# MAIN.net
KiCad netlist of a schematic drawn in Altium Designer
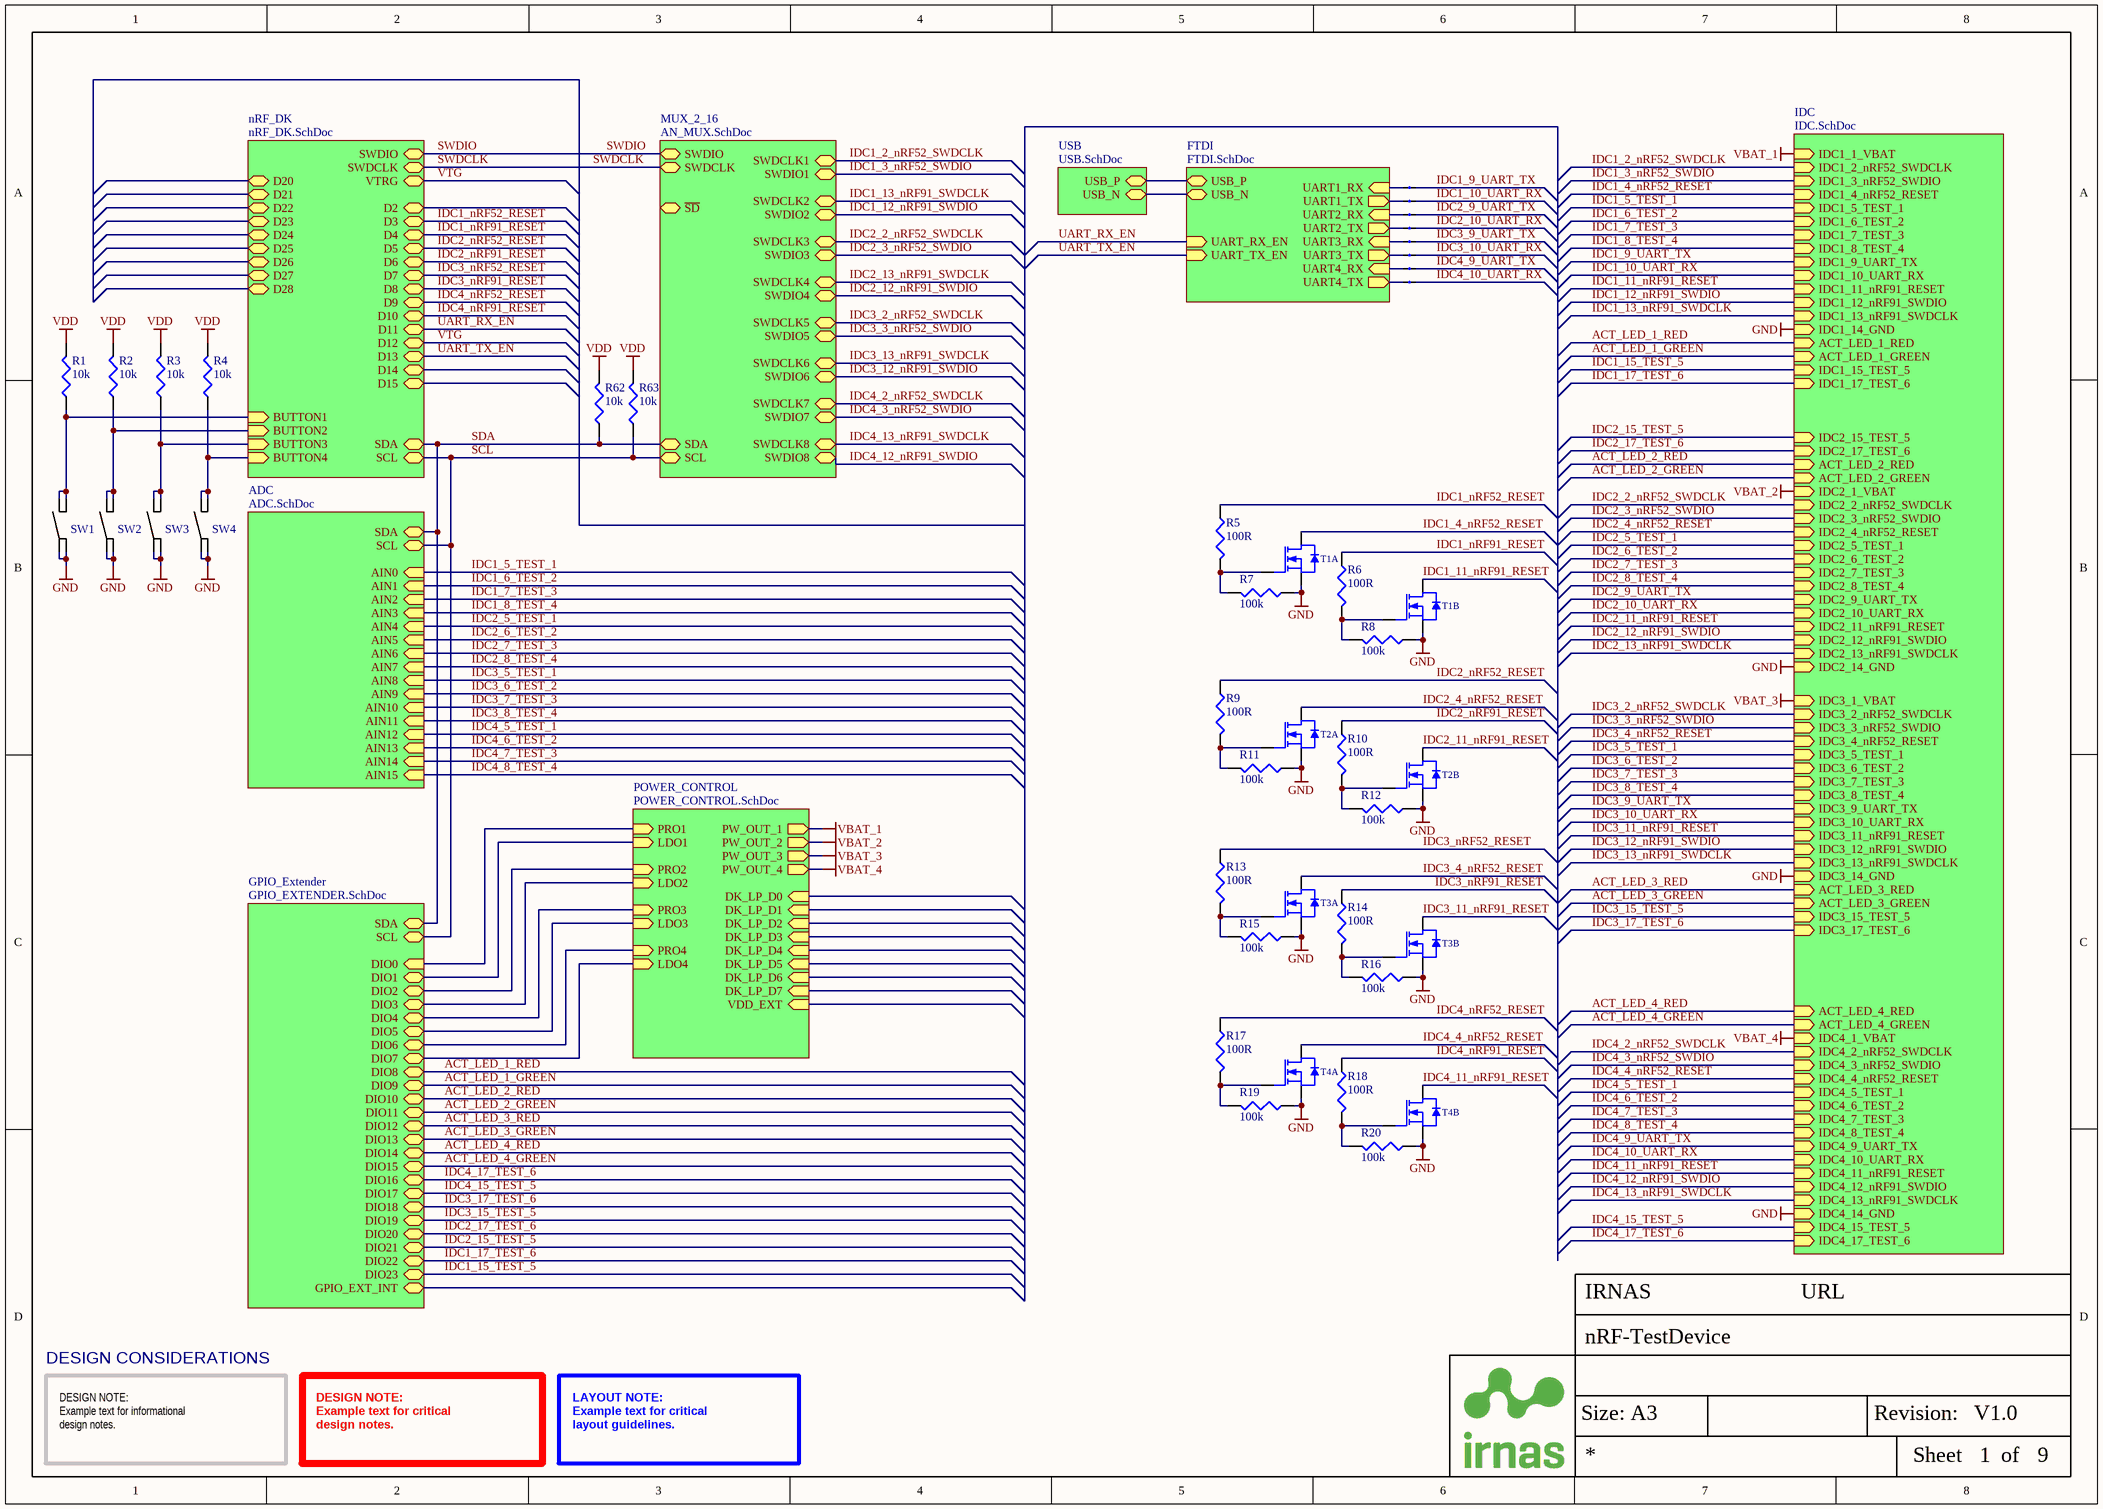
[diagram p0: MAIN.SchDoc]

(export (version "E")
  (design (tool "Eeschema 10.0.6"))
  (components
    (comp (ref "NT1")
      (value "~")
      (footprint "2 PIN STARPOINT")
      (description "Starpoint")
      (libsource (lib "Passive") (part "NetTie"))
    )
    (comp (ref "NT2")
      (value "~")
      (footprint "2 PIN STARPOINT")
      (description "Starpoint")
      (libsource (lib "Passive") (part "NetTie"))
    )
    (comp (ref "NT3")
      (value "~")
      (footprint "2 PIN STARPOINT")
      (description "Starpoint")
      (libsource (lib "Passive") (part "NetTie"))
    )
    (comp (ref "NT4")
      (value "~")
      (footprint "2 PIN STARPOINT")
      (description "Starpoint")
      (libsource (lib "Passive") (part "NetTie"))
    )
    (comp (ref "NT5")
      (value "~")
      (footprint "2 PIN STARPOINT")
      (description "Starpoint")
      (libsource (lib "Passive") (part "NetTie"))
    )
    (comp (ref "NT6")
      (value "~")
      (footprint "2 PIN STARPOINT")
      (description "Starpoint")
      (libsource (lib "Passive") (part "NetTie"))
    )
    (comp (ref "NT7")
      (value "~")
      (footprint "2 PIN STARPOINT")
      (description "Starpoint")
      (libsource (lib "Passive") (part "NetTie"))
    )
    (comp (ref "NT8")
      (value "~")
      (footprint "2 PIN STARPOINT")
      (description "Starpoint")
      (libsource (lib "Passive") (part "NetTie"))
    )
    (comp (ref "R1")
      (value "10k")
      (footprint "RES0402")
      (fields
        (field (name "MANUFACTURER") "Multicomp")
        (field (name "MANUFACTURER PART NUMBER") "MCWR04X1002FTL")
        (field (name "TOLERANCE") "1%")
      )
      (libsource (lib "Passive") (part "R - 10k/0402"))
    )
    (comp (ref "R2")
      (value "10k")
      (footprint "RES0402")
      (fields
        (field (name "MANUFACTURER") "Multicomp")
        (field (name "MANUFACTURER PART NUMBER") "MCWR04X1002FTL")
        (field (name "TOLERANCE") "1%")
      )
      (libsource (lib "Passive") (part "R - 10k/0402"))
    )
    (comp (ref "R3")
      (value "10k")
      (footprint "RES0402")
      (fields
        (field (name "MANUFACTURER") "Multicomp")
        (field (name "MANUFACTURER PART NUMBER") "MCWR04X1002FTL")
        (field (name "TOLERANCE") "1%")
      )
      (libsource (lib "Passive") (part "R - 10k/0402"))
    )
    (comp (ref "R4")
      (value "10k")
      (footprint "RES0402")
      (fields
        (field (name "MANUFACTURER") "Multicomp")
        (field (name "MANUFACTURER PART NUMBER") "MCWR04X1002FTL")
        (field (name "TOLERANCE") "1%")
      )
      (libsource (lib "Passive") (part "R - 10k/0402"))
    )
    (comp (ref "R5")
      (value "100R")
      (footprint "RES0402")
      (fields
        (field (name "MANUFACTURER") "Multicomp")
        (field (name "MANUFACTURER PART NUMBER") "MCMR04X1000FTL")
        (field (name "TOLERANCE") "1%")
      )
      (libsource (lib "Passive") (part "R - 100R/0402"))
    )
    (comp (ref "R6")
      (value "100R")
      (footprint "RES0402")
      (fields
        (field (name "MANUFACTURER") "Multicomp")
        (field (name "MANUFACTURER PART NUMBER") "MCMR04X1000FTL")
        (field (name "TOLERANCE") "1%")
      )
      (libsource (lib "Passive") (part "R - 100R/0402"))
    )
    (comp (ref "R7")
      (value "100k")
      (footprint "RES0402")
      (description "MULTICOMP   MCWR04X1003FTL   RES, THICK FILM, 100KOHM, 1%, 0.0625W")
      (fields
        (field (name "MANUFACTURER") "Multicomp")
        (field (name "MANUFACTURER PART NUMBER") "MCWR04X1003FTL")
      )
      (libsource (lib "Passive") (part "R - 100k/0402"))
    )
    (comp (ref "R8")
      (value "100k")
      (footprint "RES0402")
      (description "MULTICOMP   MCWR04X1003FTL   RES, THICK FILM, 100KOHM, 1%, 0.0625W")
      (fields
        (field (name "MANUFACTURER") "Multicomp")
        (field (name "MANUFACTURER PART NUMBER") "MCWR04X1003FTL")
      )
      (libsource (lib "Passive") (part "R - 100k/0402"))
    )
    (comp (ref "R9")
      (value "100R")
      (footprint "RES0402")
      (fields
        (field (name "MANUFACTURER") "Multicomp")
        (field (name "MANUFACTURER PART NUMBER") "MCMR04X1000FTL")
        (field (name "TOLERANCE") "1%")
      )
      (libsource (lib "Passive") (part "R - 100R/0402"))
    )
    (comp (ref "R10")
      (value "100R")
      (footprint "RES0402")
      (fields
        (field (name "MANUFACTURER") "Multicomp")
        (field (name "MANUFACTURER PART NUMBER") "MCMR04X1000FTL")
        (field (name "TOLERANCE") "1%")
      )
      (libsource (lib "Passive") (part "R - 100R/0402"))
    )
    (comp (ref "R11")
      (value "100k")
      (footprint "RES0402")
      (description "MULTICOMP   MCWR04X1003FTL   RES, THICK FILM, 100KOHM, 1%, 0.0625W")
      (fields
        (field (name "MANUFACTURER") "Multicomp")
        (field (name "MANUFACTURER PART NUMBER") "MCWR04X1003FTL")
      )
      (libsource (lib "Passive") (part "R - 100k/0402"))
    )
    (comp (ref "R12")
      (value "100k")
      (footprint "RES0402")
      (description "MULTICOMP   MCWR04X1003FTL   RES, THICK FILM, 100KOHM, 1%, 0.0625W")
      (fields
        (field (name "MANUFACTURER") "Multicomp")
        (field (name "MANUFACTURER PART NUMBER") "MCWR04X1003FTL")
      )
      (libsource (lib "Passive") (part "R - 100k/0402"))
    )
    (comp (ref "R13")
      (value "100R")
      (footprint "RES0402")
      (fields
        (field (name "MANUFACTURER") "Multicomp")
        (field (name "MANUFACTURER PART NUMBER") "MCMR04X1000FTL")
        (field (name "TOLERANCE") "1%")
      )
      (libsource (lib "Passive") (part "R - 100R/0402"))
    )
    (comp (ref "R14")
      (value "100R")
      (footprint "RES0402")
      (fields
        (field (name "MANUFACTURER") "Multicomp")
        (field (name "MANUFACTURER PART NUMBER") "MCMR04X1000FTL")
        (field (name "TOLERANCE") "1%")
      )
      (libsource (lib "Passive") (part "R - 100R/0402"))
    )
    (comp (ref "R15")
      (value "100k")
      (footprint "RES0402")
      (description "MULTICOMP   MCWR04X1003FTL   RES, THICK FILM, 100KOHM, 1%, 0.0625W")
      (fields
        (field (name "MANUFACTURER") "Multicomp")
        (field (name "MANUFACTURER PART NUMBER") "MCWR04X1003FTL")
      )
      (libsource (lib "Passive") (part "R - 100k/0402"))
    )
    (comp (ref "R16")
      (value "100k")
      (footprint "RES0402")
      (description "MULTICOMP   MCWR04X1003FTL   RES, THICK FILM, 100KOHM, 1%, 0.0625W")
      (fields
        (field (name "MANUFACTURER") "Multicomp")
        (field (name "MANUFACTURER PART NUMBER") "MCWR04X1003FTL")
      )
      (libsource (lib "Passive") (part "R - 100k/0402"))
    )
    (comp (ref "R17")
      (value "100R")
      (footprint "RES0402")
      (fields
        (field (name "MANUFACTURER") "Multicomp")
        (field (name "MANUFACTURER PART NUMBER") "MCMR04X1000FTL")
        (field (name "TOLERANCE") "1%")
      )
      (libsource (lib "Passive") (part "R - 100R/0402"))
    )
    (comp (ref "R18")
      (value "100R")
      (footprint "RES0402")
      (fields
        (field (name "MANUFACTURER") "Multicomp")
        (field (name "MANUFACTURER PART NUMBER") "MCMR04X1000FTL")
        (field (name "TOLERANCE") "1%")
      )
      (libsource (lib "Passive") (part "R - 100R/0402"))
    )
    (comp (ref "R19")
      (value "100k")
      (footprint "RES0402")
      (description "MULTICOMP   MCWR04X1003FTL   RES, THICK FILM, 100KOHM, 1%, 0.0625W")
      (fields
        (field (name "MANUFACTURER") "Multicomp")
        (field (name "MANUFACTURER PART NUMBER") "MCWR04X1003FTL")
      )
      (libsource (lib "Passive") (part "R - 100k/0402"))
    )
    (comp (ref "R20")
      (value "100k")
      (footprint "RES0402")
      (description "MULTICOMP   MCWR04X1003FTL   RES, THICK FILM, 100KOHM, 1%, 0.0625W")
      (fields
        (field (name "MANUFACTURER") "Multicomp")
        (field (name "MANUFACTURER PART NUMBER") "MCWR04X1003FTL")
      )
      (libsource (lib "Passive") (part "R - 100k/0402"))
    )
    (comp (ref "R62")
      (value "10k")
      (footprint "RES0402")
      (fields
        (field (name "MANUFACTURER") "Multicomp")
        (field (name "MANUFACTURER PART NUMBER") "MCWR04X1002FTL")
        (field (name "TOLERANCE") "1%")
      )
      (libsource (lib "Passive") (part "R - 10k/0402"))
    )
    (comp (ref "R63")
      (value "10k")
      (footprint "RES0402")
      (fields
        (field (name "MANUFACTURER") "Multicomp")
        (field (name "MANUFACTURER PART NUMBER") "MCWR04X1002FTL")
        (field (name "TOLERANCE") "1%")
      )
      (libsource (lib "Passive") (part "R - 10k/0402"))
    )
    (comp (ref "SW1")
      (value "PTS645SL50-2 LFS")
      (footprint "Tactile Switch THT")
      (description "Tactile Switch, PT645 Series, Top Actuated, Through Hole, Round Button, 130 gf, 50mA at 12VDC")
      (fields (field (name "MANUFACTURER") "C&K"))
      (libsource (lib "Mechanical") (part "SW - PTS645SL50-2 LFS"))
    )
    (comp (ref "SW2")
      (value "PTS645SL50-2 LFS")
      (footprint "Tactile Switch THT")
      (description "Tactile Switch, PT645 Series, Top Actuated, Through Hole, Round Button, 130 gf, 50mA at 12VDC")
      (fields (field (name "MANUFACTURER") "C&K"))
      (libsource (lib "Mechanical") (part "SW - PTS645SL50-2 LFS"))
    )
    (comp (ref "SW3")
      (value "PTS645SL50-2 LFS")
      (footprint "Tactile Switch THT")
      (description "Tactile Switch, PT645 Series, Top Actuated, Through Hole, Round Button, 130 gf, 50mA at 12VDC")
      (fields (field (name "MANUFACTURER") "C&K"))
      (libsource (lib "Mechanical") (part "SW - PTS645SL50-2 LFS"))
    )
    (comp (ref "SW4")
      (value "PTS645SL50-2 LFS")
      (footprint "Tactile Switch THT")
      (description "Tactile Switch, PT645 Series, Top Actuated, Through Hole, Round Button, 130 gf, 50mA at 12VDC")
      (fields (field (name "MANUFACTURER") "C&K"))
      (libsource (lib "Mechanical") (part "SW - PTS645SL50-2 LFS"))
    )
    (comp (ref "T1")
      (value "NTZD3154NT1G")
      (footprint "SOT-563")
      (description "Dual MOSFET, Dual N Channel, 540 mA, 20 V, 0.4 ohm, 4.5 V, 1 V")
      (fields (field (name "AUTHOR") "Ciril Golob"))
      (libsource (lib "Active") (part "T_M - NTZD3154NT1G"))
    )
    (comp (ref "T2")
      (value "NTZD3154NT1G")
      (footprint "SOT-563")
      (description "Dual MOSFET, Dual N Channel, 540 mA, 20 V, 0.4 ohm, 4.5 V, 1 V")
      (fields (field (name "AUTHOR") "Ciril Golob"))
      (libsource (lib "Active") (part "T_M - NTZD3154NT1G"))
    )
    (comp (ref "T3")
      (value "NTZD3154NT1G")
      (footprint "SOT-563")
      (description "Dual MOSFET, Dual N Channel, 540 mA, 20 V, 0.4 ohm, 4.5 V, 1 V")
      (fields (field (name "AUTHOR") "Ciril Golob"))
      (libsource (lib "Active") (part "T_M - NTZD3154NT1G"))
    )
    (comp (ref "T4")
      (value "NTZD3154NT1G")
      (footprint "SOT-563")
      (description "Dual MOSFET, Dual N Channel, 540 mA, 20 V, 0.4 ohm, 4.5 V, 1 V")
      (fields (field (name "AUTHOR") "Ciril Golob"))
      (libsource (lib "Active") (part "T_M - NTZD3154NT1G"))
    )
  )
  (nets
    (net (code "9") (name "/BUTTON1") (class "Default")
      (node (ref "R1") (pin "1") (pinfunction "1_1") (pintype "passive"))
      (node (ref "SW1") (pin "3") (pinfunction "3_3") (pintype "passive"))
      (node (ref "SW1") (pin "4") (pinfunction "4_4") (pintype "passive"))
    )
    (net (code "10") (name "/BUTTON2") (class "Default")
      (node (ref "R2") (pin "1") (pinfunction "1_1") (pintype "passive"))
      (node (ref "SW2") (pin "3") (pinfunction "3_3") (pintype "passive"))
      (node (ref "SW2") (pin "4") (pinfunction "4_4") (pintype "passive"))
    )
    (net (code "11") (name "/BUTTON3") (class "Default")
      (node (ref "R3") (pin "1") (pinfunction "1_1") (pintype "passive"))
      (node (ref "SW3") (pin "3") (pinfunction "3_3") (pintype "passive"))
      (node (ref "SW3") (pin "4") (pinfunction "4_4") (pintype "passive"))
    )
    (net (code "12") (name "/BUTTON4") (class "Default")
      (node (ref "R4") (pin "1") (pinfunction "1_1") (pintype "passive"))
      (node (ref "SW4") (pin "3") (pinfunction "3_3") (pintype "passive"))
      (node (ref "SW4") (pin "4") (pinfunction "4_4") (pintype "passive"))
    )
    (net (code "44") (name "/IDC1_4_nRF52_RESET") (class "Default")
      (node (ref "T1") (pin "6") (pinfunction "D1_6") (pintype "passive"))
    )
    (net (code "49") (name "/IDC1_9_UART_TX") (class "Default")
      (node (ref "NT1") (pin "2") (pintype "passive"))
    )
    (net (code "50") (name "/IDC1_10_UART_RX") (class "Default")
      (node (ref "NT2") (pin "2") (pintype "passive"))
    )
    (net (code "51") (name "/IDC1_11_nRF91_RESET") (class "Default")
      (node (ref "T1") (pin "3") (pinfunction "D2_3") (pintype "passive"))
    )
    (net (code "56") (name "/IDC1_nRF52_RESET") (class "Default")
      (node (ref "R5") (pin "1") (pinfunction "1_1") (pintype "passive"))
    )
    (net (code "57") (name "/IDC1_nRF91_RESET") (class "Default")
      (node (ref "R6") (pin "1") (pinfunction "1_1") (pintype "passive"))
    )
    (net (code "60") (name "/IDC2_4_nRF52_RESET") (class "Default")
      (node (ref "T2") (pin "6") (pinfunction "D1_6") (pintype "passive"))
    )
    (net (code "65") (name "/IDC2_9_UART_TX") (class "Default")
      (node (ref "NT3") (pin "2") (pintype "passive"))
    )
    (net (code "66") (name "/IDC2_10_UART_RX") (class "Default")
      (node (ref "NT4") (pin "2") (pintype "passive"))
    )
    (net (code "67") (name "/IDC2_11_nRF91_RESET") (class "Default")
      (node (ref "T2") (pin "3") (pinfunction "D2_3") (pintype "passive"))
    )
    (net (code "72") (name "/IDC2_nRF52_RESET") (class "Default")
      (node (ref "R9") (pin "1") (pinfunction "1_1") (pintype "passive"))
    )
    (net (code "73") (name "/IDC2_nRF91_RESET") (class "Default")
      (node (ref "R10") (pin "1") (pinfunction "1_1") (pintype "passive"))
    )
    (net (code "76") (name "/IDC3_4_nRF52_RESET") (class "Default")
      (node (ref "T3") (pin "6") (pinfunction "D1_6") (pintype "passive"))
    )
    (net (code "81") (name "/IDC3_9_UART_TX") (class "Default")
      (node (ref "NT5") (pin "2") (pintype "passive"))
    )
    (net (code "82") (name "/IDC3_10_UART_RX") (class "Default")
      (node (ref "NT6") (pin "2") (pintype "passive"))
    )
    (net (code "83") (name "/IDC3_11_nRF91_RESET") (class "Default")
      (node (ref "T3") (pin "3") (pinfunction "D2_3") (pintype "passive"))
    )
    (net (code "88") (name "/IDC3_nRF52_RESET") (class "Default")
      (node (ref "R13") (pin "1") (pinfunction "1_1") (pintype "passive"))
    )
    (net (code "89") (name "/IDC3_nRF91_RESET") (class "Default")
      (node (ref "R14") (pin "1") (pinfunction "1_1") (pintype "passive"))
    )
    (net (code "92") (name "/IDC4_4_nRF52_RESET") (class "Default")
      (node (ref "T4") (pin "6") (pinfunction "D1_6") (pintype "passive"))
    )
    (net (code "97") (name "/IDC4_9_UART_TX") (class "Default")
      (node (ref "NT7") (pin "2") (pintype "passive"))
    )
    (net (code "98") (name "/IDC4_10_UART_RX") (class "Default")
      (node (ref "NT8") (pin "2") (pintype "passive"))
    )
    (net (code "99") (name "/IDC4_11_nRF91_RESET") (class "Default")
      (node (ref "T4") (pin "3") (pinfunction "D2_3") (pintype "passive"))
    )
    (net (code "104") (name "/IDC4_nRF52_RESET") (class "Default")
      (node (ref "R17") (pin "1") (pinfunction "1_1") (pintype "passive"))
    )
    (net (code "105") (name "/IDC4_nRF91_RESET") (class "Default")
      (node (ref "R18") (pin "1") (pinfunction "1_1") (pintype "passive"))
    )
    (net (code "106") (name "/SCL") (class "Default")
      (node (ref "R63") (pin "1") (pinfunction "1_1") (pintype "passive"))
    )
    (net (code "107") (name "/SDA") (class "Default")
      (node (ref "R62") (pin "1") (pinfunction "1_1") (pintype "passive"))
    )
    (net (code "110") (name "/UART1_RX") (class "Default") (node (ref "NT1") (pin "1") (pintype "passive")))
    (net (code "111") (name "/UART1_TX") (class "Default") (node (ref "NT2") (pin "1") (pintype "passive")))
    (net (code "112") (name "/UART2_RX") (class "Default") (node (ref "NT3") (pin "1") (pintype "passive")))
    (net (code "113") (name "/UART2_TX") (class "Default") (node (ref "NT4") (pin "1") (pintype "passive")))
    (net (code "114") (name "/UART3_RX") (class "Default") (node (ref "NT5") (pin "1") (pintype "passive")))
    (net (code "115") (name "/UART3_TX") (class "Default") (node (ref "NT6") (pin "1") (pintype "passive")))
    (net (code "116") (name "/UART4_RX") (class "Default") (node (ref "NT7") (pin "1") (pintype "passive")))
    (net (code "117") (name "/UART4_TX") (class "Default") (node (ref "NT8") (pin "1") (pintype "passive")))
    (net (code "125") (name "GND") (class "Default")
      (node (ref "R11") (pin "1") (pinfunction "1_1") (pintype "passive"))
      (node (ref "R12") (pin "1") (pinfunction "1_1") (pintype "passive"))
      (node (ref "R15") (pin "1") (pinfunction "1_1") (pintype "passive"))
      (node (ref "R16") (pin "1") (pinfunction "1_1") (pintype "passive"))
      (node (ref "R19") (pin "1") (pinfunction "1_1") (pintype "passive"))
      (node (ref "R20") (pin "1") (pinfunction "1_1") (pintype "passive"))
      (node (ref "R7") (pin "1") (pinfunction "1_1") (pintype "passive"))
      (node (ref "R8") (pin "1") (pinfunction "1_1") (pintype "passive"))
      (node (ref "SW1") (pin "1") (pinfunction "1_1") (pintype "passive"))
      (node (ref "SW1") (pin "2") (pinfunction "2_2") (pintype "passive"))
      (node (ref "SW2") (pin "1") (pinfunction "1_1") (pintype "passive"))
      (node (ref "SW2") (pin "2") (pinfunction "2_2") (pintype "passive"))
      (node (ref "SW3") (pin "1") (pinfunction "1_1") (pintype "passive"))
      (node (ref "SW3") (pin "2") (pinfunction "2_2") (pintype "passive"))
      (node (ref "SW4") (pin "1") (pinfunction "1_1") (pintype "passive"))
      (node (ref "SW4") (pin "2") (pinfunction "2_2") (pintype "passive"))
      (node (ref "T1") (pin "1") (pinfunction "S1_1") (pintype "passive"))
      (node (ref "T1") (pin "4") (pinfunction "S2_4") (pintype "passive"))
      (node (ref "T2") (pin "1") (pinfunction "S1_1") (pintype "passive"))
      (node (ref "T2") (pin "4") (pinfunction "S2_4") (pintype "passive"))
      (node (ref "T3") (pin "1") (pinfunction "S1_1") (pintype "passive"))
      (node (ref "T3") (pin "4") (pinfunction "S2_4") (pintype "passive"))
      (node (ref "T4") (pin "1") (pinfunction "S1_1") (pintype "passive"))
      (node (ref "T4") (pin "4") (pinfunction "S2_4") (pintype "passive"))
    )
    (net (code "126") (name "Net-(T1A-G1)") (class "Default")
      (node (ref "R5") (pin "2") (pinfunction "2_2") (pintype "passive"))
      (node (ref "R7") (pin "2") (pinfunction "2_2") (pintype "passive"))
      (node (ref "T1") (pin "2") (pinfunction "G1_2") (pintype "passive"))
    )
    (net (code "127") (name "Net-(T1B-G2)") (class "Default")
      (node (ref "R6") (pin "2") (pinfunction "2_2") (pintype "passive"))
      (node (ref "R8") (pin "2") (pinfunction "2_2") (pintype "passive"))
      (node (ref "T1") (pin "5") (pinfunction "G2_5") (pintype "passive"))
    )
    (net (code "128") (name "Net-(T2A-G1)") (class "Default")
      (node (ref "R11") (pin "2") (pinfunction "2_2") (pintype "passive"))
      (node (ref "R9") (pin "2") (pinfunction "2_2") (pintype "passive"))
      (node (ref "T2") (pin "2") (pinfunction "G1_2") (pintype "passive"))
    )
    (net (code "129") (name "Net-(T2B-G2)") (class "Default")
      (node (ref "R10") (pin "2") (pinfunction "2_2") (pintype "passive"))
      (node (ref "R12") (pin "2") (pinfunction "2_2") (pintype "passive"))
      (node (ref "T2") (pin "5") (pinfunction "G2_5") (pintype "passive"))
    )
    (net (code "130") (name "Net-(T3A-G1)") (class "Default")
      (node (ref "R13") (pin "2") (pinfunction "2_2") (pintype "passive"))
      (node (ref "R15") (pin "2") (pinfunction "2_2") (pintype "passive"))
      (node (ref "T3") (pin "2") (pinfunction "G1_2") (pintype "passive"))
    )
    (net (code "131") (name "Net-(T3B-G2)") (class "Default")
      (node (ref "R14") (pin "2") (pinfunction "2_2") (pintype "passive"))
      (node (ref "R16") (pin "2") (pinfunction "2_2") (pintype "passive"))
      (node (ref "T3") (pin "5") (pinfunction "G2_5") (pintype "passive"))
    )
    (net (code "132") (name "Net-(T4A-G1)") (class "Default")
      (node (ref "R17") (pin "2") (pinfunction "2_2") (pintype "passive"))
      (node (ref "R19") (pin "2") (pinfunction "2_2") (pintype "passive"))
      (node (ref "T4") (pin "2") (pinfunction "G1_2") (pintype "passive"))
    )
    (net (code "133") (name "Net-(T4B-G2)") (class "Default")
      (node (ref "R18") (pin "2") (pinfunction "2_2") (pintype "passive"))
      (node (ref "R20") (pin "2") (pinfunction "2_2") (pintype "passive"))
      (node (ref "T4") (pin "5") (pinfunction "G2_5") (pintype "passive"))
    )
    (net (code "138") (name "VDD") (class "Default")
      (node (ref "R1") (pin "2") (pinfunction "2_2") (pintype "passive"))
      (node (ref "R2") (pin "2") (pinfunction "2_2") (pintype "passive"))
      (node (ref "R3") (pin "2") (pinfunction "2_2") (pintype "passive"))
      (node (ref "R4") (pin "2") (pinfunction "2_2") (pintype "passive"))
      (node (ref "R62") (pin "2") (pinfunction "2_2") (pintype "passive"))
      (node (ref "R63") (pin "2") (pinfunction "2_2") (pintype "passive"))
    )
  )
)
